# V4-MySensors-LoRa-V006.net
KiCad netlist of a schematic drawn in EAGLE
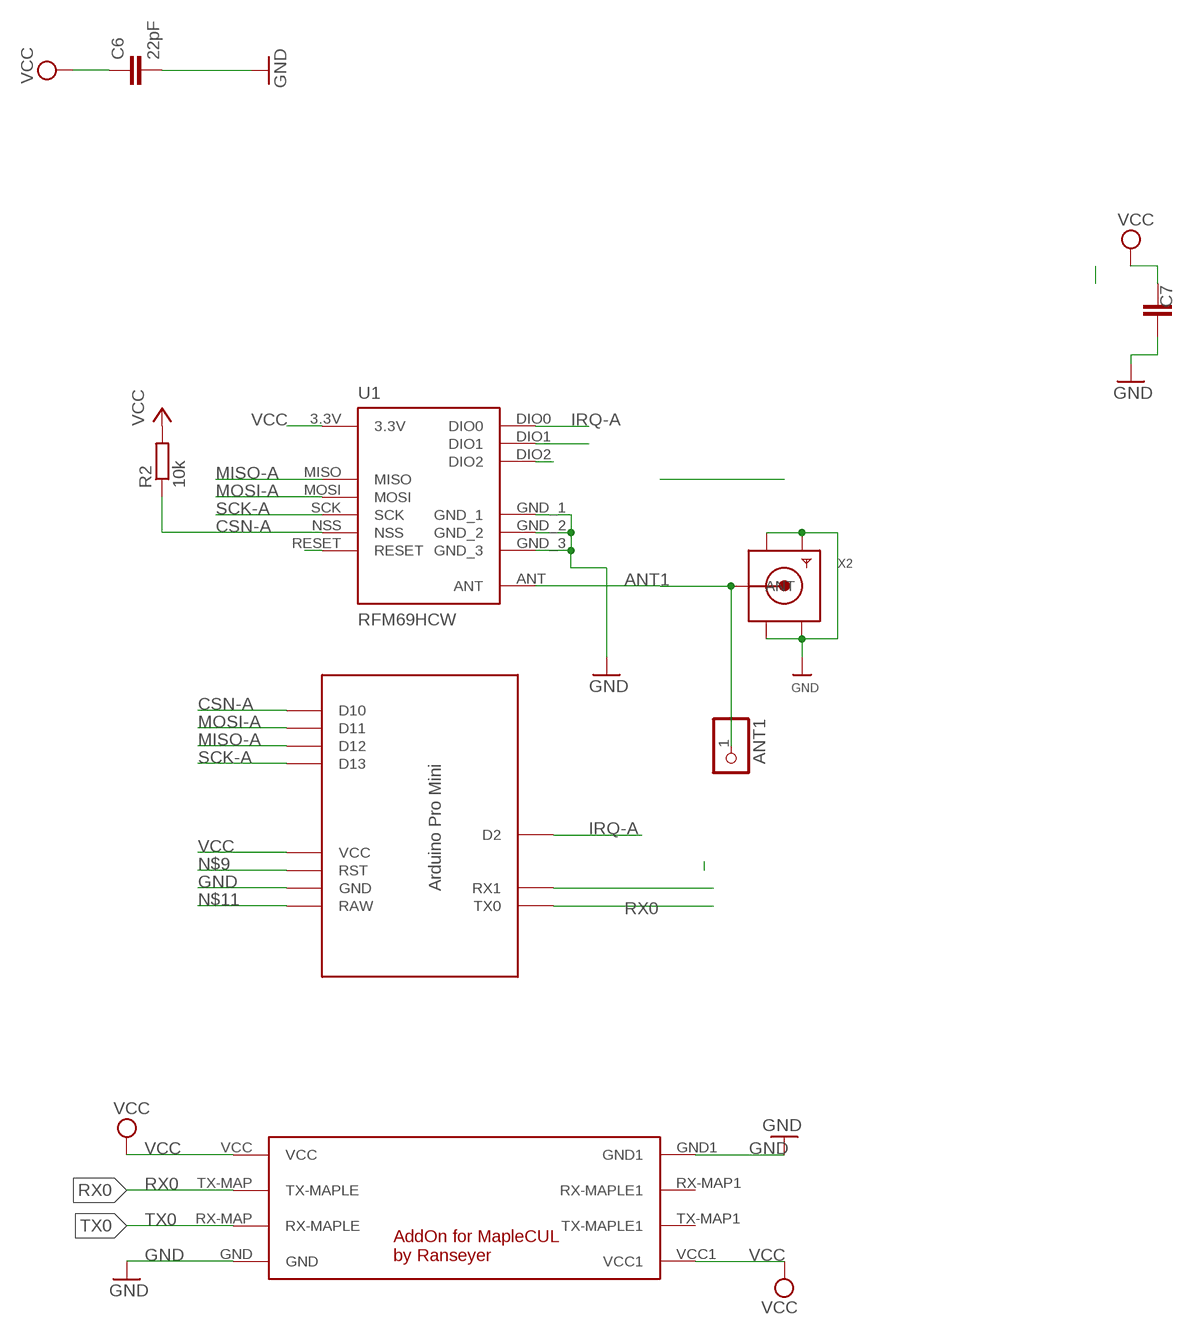
[diagram p0: schematic, sheet 1]

(export (version "E")
  (design (tool "Eeschema 10.0.6"))
  (components
    (comp (ref "ANT1")
      (value "PINHD-1X1")
      (footprint "eagle-import:1X01")
      (libsource (lib "eagle-import") (part "PINHD-1X1"))
    )
    (comp (ref "C6")
      (value "22pF")
      (footprint "eagle-import:C0805")
      (libsource (lib "eagle-import") (part "C-EUC0805"))
    )
    (comp (ref "C7")
      (value "C-EUC1812")
      (footprint "eagle-import:C1812")
      (libsource (lib "eagle-import") (part "C-EUC1812"))
    )
    (comp (ref "R2")
      (value "10k")
      (footprint "eagle-import:M0805")
      (libsource (lib "eagle-import") (part "R-EU_M0805"))
    )
    (comp (ref "U$1")
      (value "MARTIN-PROMINI-SPI")
      (footprint "eagle-import:MARTIN-PRO-SPI")
      (libsource (lib "eagle-import") (part "MARTIN-PROMINI-SPI"))
    )
    (comp (ref "U$2")
      (value "MAPLE-CUL-ADDON-V01")
      (footprint "eagle-import:MAPLE-CUL-V01")
      (libsource (lib "eagle-import") (part "MAPLE-CUL-ADDON-V01"))
    )
    (comp (ref "U1")
      (value "RFM69HCW")
      (footprint "eagle-import:RFM69HCW-XXXS2")
      (libsource (lib "eagle-import") (part "RFM69HCW"))
    )
    (comp (ref "X2")
      (value "SMACONNECTOR_EDGE")
      (footprint "eagle-import:SMA_EDGELAUNCH")
      (libsource (lib "eagle-import") (part "SMACONNECTOR_EDGE"))
    )
  )
  (nets
    (net (code "1") (name "/ANT1") (class "Default")
      (node (ref "ANT1") (pin "1") (pinfunction "1_1") (pintype "passive"))
      (node (ref "U1") (pin "ANT") (pinfunction "ANT_ANT") (pintype "passive"))
      (node (ref "X2") (pin "P") (pinfunction "ANT_P") (pintype "bidirectional"))
    )
    (net (code "2") (name "/CSN-A") (class "Default")
      (node (ref "R2") (pin "1") (pinfunction "1_1") (pintype "passive"))
      (node (ref "U$1") (pin "D10") (pinfunction "D10_D10") (pintype "bidirectional"))
      (node (ref "U1") (pin "NSS") (pinfunction "NSS_NSS") (pintype "input"))
    )
    (net (code "3") (name "/IRQ-A") (class "Default")
      (node (ref "U$1") (pin "D2") (pinfunction "D2_D2") (pintype "bidirectional"))
      (node (ref "U1") (pin "DIO0") (pinfunction "DIO0_DIO0") (pintype "bidirectional"))
    )
    (net (code "4") (name "/MISO-A") (class "Default")
      (node (ref "U$1") (pin "D12") (pinfunction "D12_D12") (pintype "bidirectional"))
      (node (ref "U1") (pin "MISO") (pinfunction "MISO_MISO") (pintype "bidirectional"))
    )
    (net (code "5") (name "/MOSI-A") (class "Default")
      (node (ref "U$1") (pin "D11") (pinfunction "D11_D11") (pintype "bidirectional"))
      (node (ref "U1") (pin "MOSI") (pinfunction "MOSI_MOSI") (pintype "input"))
    )
    (net (code "6") (name "/N$9") (class "Default")
      (node (ref "U$1") (pin "RST") (pinfunction "RST_RST") (pintype "bidirectional"))
    )
    (net (code "7") (name "/N$11") (class "Default")
      (node (ref "U$1") (pin "RAW") (pinfunction "RAW_RAW") (pintype "bidirectional"))
    )
    (net (code "8") (name "/SCK-A") (class "Default")
      (node (ref "U$1") (pin "D13") (pinfunction "D13_D13") (pintype "bidirectional"))
      (node (ref "U1") (pin "SCK") (pinfunction "SCK_SCK") (pintype "input"))
    )
    (net (code "9") (name "GND") (class "Default")
      (node (ref "C6") (pin "2") (pinfunction "2_2") (pintype "passive"))
      (node (ref "C7") (pin "1") (pinfunction "1_1") (pintype "passive"))
      (node (ref "U$1") (pin "GND") (pinfunction "GND_GND") (pintype "bidirectional"))
      (node (ref "U$2") (pin "GND") (pinfunction "GND_GND") (pintype "bidirectional"))
      (node (ref "U$2") (pin "GND1") (pinfunction "GND1_GND1") (pintype "bidirectional"))
      (node (ref "U1") (pin "GND_1") (pinfunction "GND_1_GND_1") (pintype "power_in"))
      (node (ref "U1") (pin "GND_2") (pinfunction "GND_2_GND_2") (pintype "power_in"))
      (node (ref "U1") (pin "GND_3") (pinfunction "GND_3_GND_3") (pintype "power_in"))
      (node (ref "X2") (pin "GND@1") (pinfunction "GND4_GND@1") (pintype "power_in"))
      (node (ref "X2") (pin "GND@2") (pinfunction "GND3_GND@2") (pintype "power_in"))
      (node (ref "X2") (pin "GND@3") (pinfunction "GND2_GND@3") (pintype "power_in"))
      (node (ref "X2") (pin "GND@4") (pinfunction "GND1_GND@4") (pintype "power_in"))
    )
    (net (code "10") (name "RX0") (class "Default")
      (node (ref "U$1") (pin "TX0") (pinfunction "TX0_TX0") (pintype "bidirectional"))
      (node (ref "U$2") (pin "TX-MAP") (pinfunction "TX-MAPLE_TX-MAP") (pintype "bidirectional"))
    )
    (net (code "11") (name "TX0") (class "Default")
      (node (ref "U$1") (pin "RX1") (pinfunction "RX1_RX1") (pintype "bidirectional"))
      (node (ref "U$2") (pin "RX-MAP") (pinfunction "RX-MAPLE_RX-MAP") (pintype "bidirectional"))
    )
    (net (code "12") (name "VCC") (class "Default")
      (node (ref "C6") (pin "1") (pinfunction "1_1") (pintype "passive"))
      (node (ref "C7") (pin "2") (pinfunction "2_2") (pintype "passive"))
      (node (ref "R2") (pin "2") (pinfunction "2_2") (pintype "passive"))
      (node (ref "U$1") (pin "VCC") (pinfunction "VCC_VCC") (pintype "bidirectional"))
      (node (ref "U$2") (pin "VCC") (pinfunction "VCC_VCC") (pintype "bidirectional"))
      (node (ref "U$2") (pin "VCC1") (pinfunction "VCC1_VCC1") (pintype "bidirectional"))
      (node (ref "U1") (pin "3.3V") (pinfunction "3.3V_3.3V") (pintype "power_in"))
    )
    (net (code "13") (name "unconnected-(U$2-RX-MAPLE1-PadRX-MAP1)") (class "Default")
      (node (ref "U$2") (pin "RX-MAP1") (pinfunction "RX-MAPLE1_RX-MAP1") (pintype "bidirectional"))
    )
    (net (code "14") (name "unconnected-(U$2-TX-MAPLE1-PadTX-MAP1)") (class "Default")
      (node (ref "U$2") (pin "TX-MAP1") (pinfunction "TX-MAPLE1_TX-MAP1") (pintype "bidirectional"))
    )
    (net (code "15") (name "unconnected-(U1-PadDIO1)") (class "Default")
      (node (ref "U1") (pin "DIO1") (pinfunction "DIO1_DIO1") (pintype "bidirectional"))
    )
    (net (code "16") (name "unconnected-(U1-PadDIO2)") (class "Default")
      (node (ref "U1") (pin "DIO2") (pinfunction "DIO2_DIO2") (pintype "bidirectional"))
    )
    (net (code "17") (name "unconnected-(U1-PadRESET)") (class "Default")
      (node (ref "U1") (pin "RESET") (pinfunction "RESET_RESET") (pintype "input"))
    )
  )
)
